# SCH_DengFOC_V3_pro.net
KiCad netlist of a schematic drawn in EasyEDA Pro
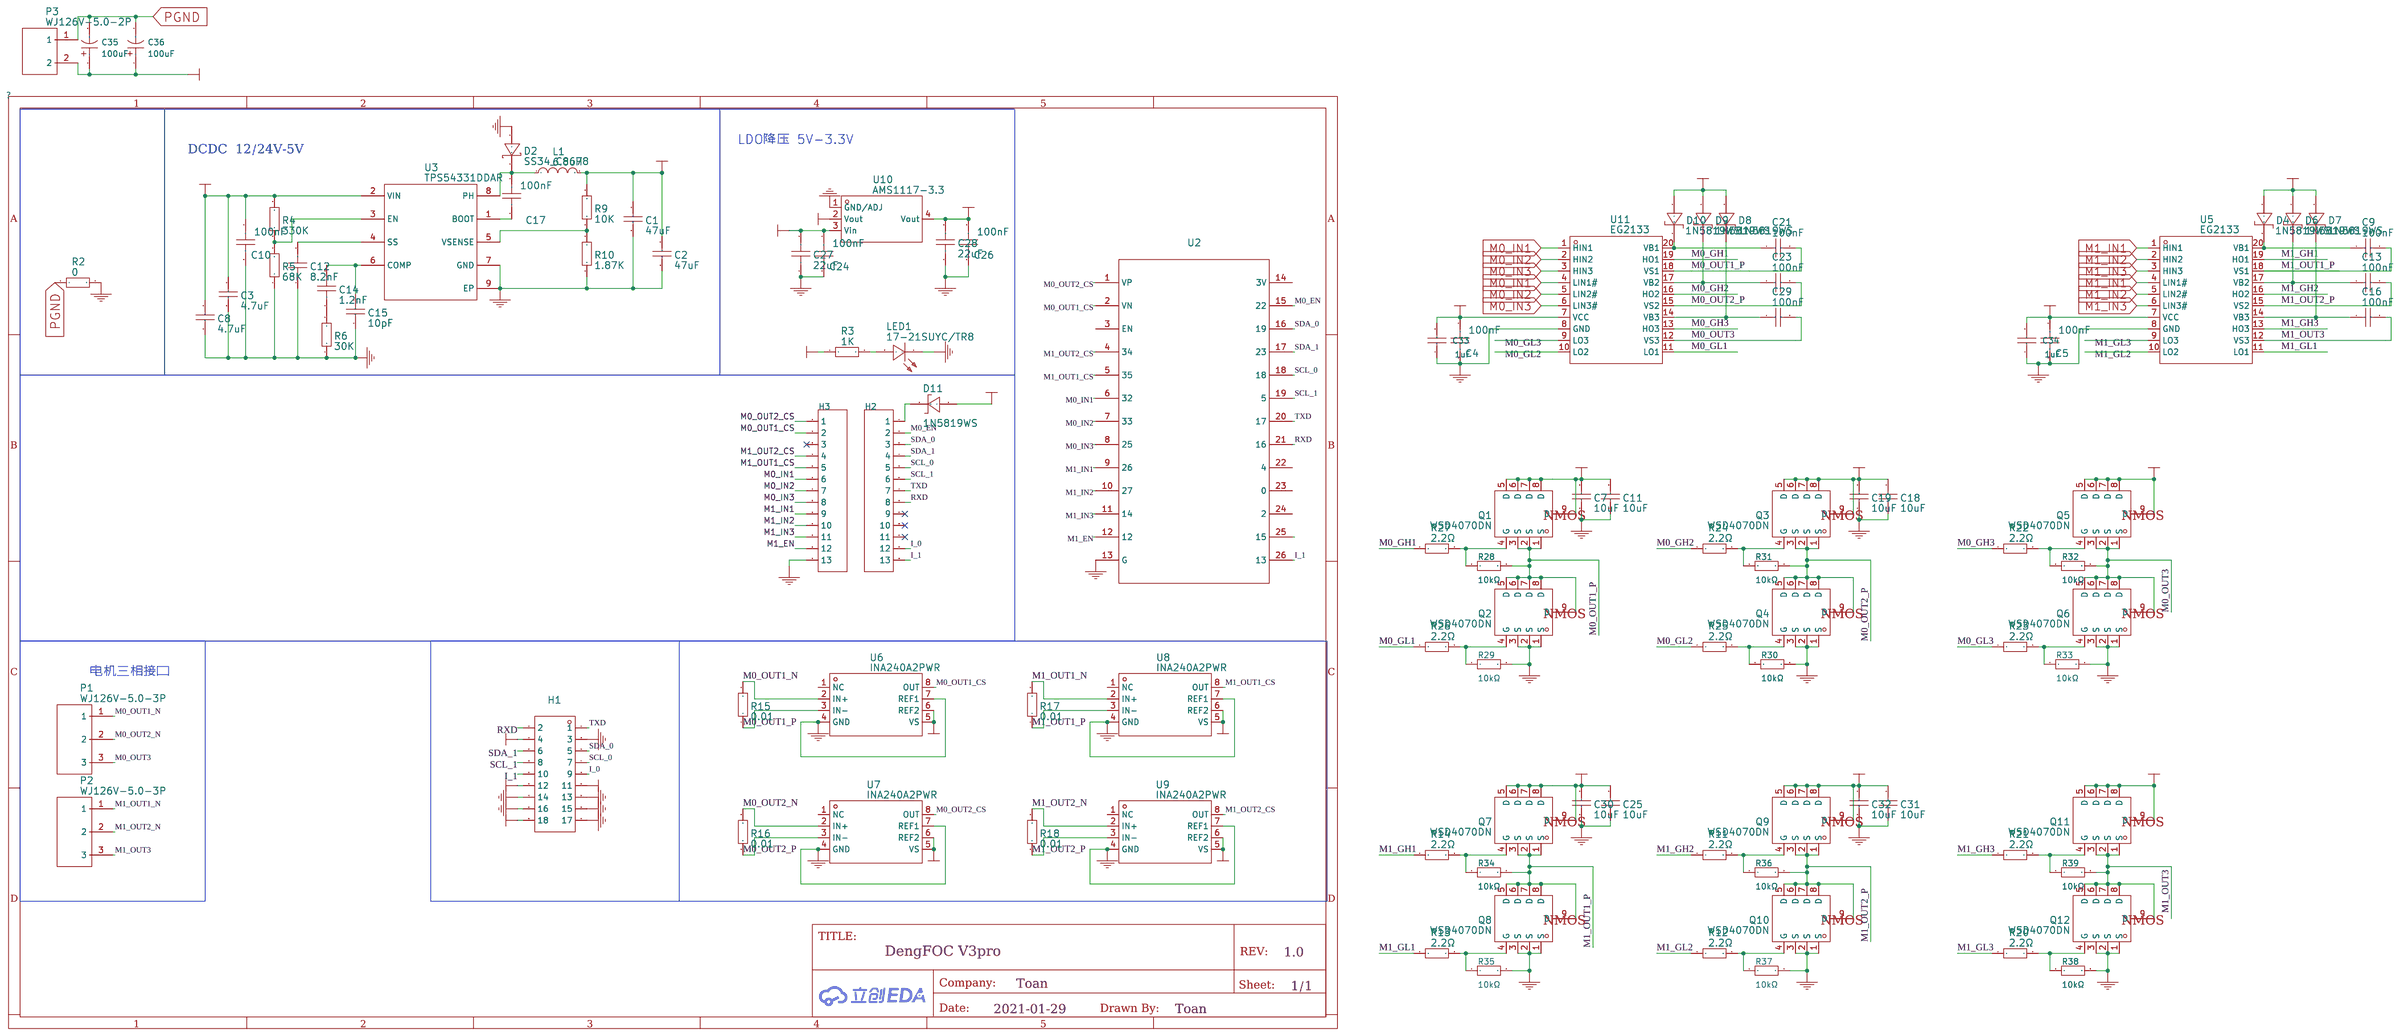
[diagram p0: schematic sheet]

(export (version "E")
  (design (tool "Eeschema 10.0.6"))
  (components
    (comp (ref "C1")
      (value "47uF")
      (footprint "easyedapro:0603")
      (fields (field (name "Manufacturer Part") "GRM188R60J476ME15D") (field (name "Manufacturer") "MuRata"))
      (libsource (lib "easyedapro") (part "47uF"))
    )
    (comp (ref "C2")
      (value "47uF")
      (footprint "easyedapro:0603")
      (fields (field (name "Manufacturer Part") "GRM188R60J476ME15D") (field (name "Manufacturer") "MuRata"))
      (libsource (lib "easyedapro") (part "47uF"))
    )
    (comp (ref "C3")
      (value "4.7uF")
      (footprint "easyedapro:0805")
      (fields (field (name "Manufacturer Part") "CL21A475KBQNNNE") (field (name "Manufacturer") "SAMSUNG"))
      (libsource (lib "easyedapro") (part "4.7uF"))
    )
    (comp (ref "C4")
      (value "100nF")
      (footprint "easyedapro:0603")
      (fields (field (name "Manufacturer Part") "CC0603KRX7R9BB104") (field (name "Manufacturer") "YAGEO"))
      (libsource (lib "") (part "100nF_1"))
    )
    (comp (ref "C5")
      (value "100nF")
      (footprint "easyedapro:0603")
      (fields (field (name "Manufacturer Part") "CC0603KRX7R9BB104") (field (name "Manufacturer") "YAGEO"))
      (libsource (lib "") (part "100nF_1"))
    )
    (comp (ref "C7")
      (value "10uF")
      (footprint "easyedapro:0805")
      (fields (field (name "Manufacturer Part") "CL21A106KAYNNNE") (field (name "Manufacturer") "SAMSUNG"))
      (libsource (lib "easyedapro") (part "10uF"))
    )
    (comp (ref "C8")
      (value "4.7uF")
      (footprint "easyedapro:0805")
      (fields (field (name "Manufacturer Part") "CL21A475KBQNNNE") (field (name "Manufacturer") "SAMSUNG"))
      (libsource (lib "easyedapro") (part "4.7uF"))
    )
    (comp (ref "C9")
      (value "100nF")
      (footprint "easyedapro:0402")
      (fields (field (name "Manufacturer Part") "CL05B104KO5NNNC") (field (name "Manufacturer") "SAMSUNG"))
      (libsource (lib "easyedapro") (part "100nF"))
    )
    (comp (ref "C10")
      (value "100nF")
      (footprint "easyedapro:0603")
      (fields (field (name "Manufacturer Part") "CC0603KRX7R9BB104") (field (name "Manufacturer") "YAGEO"))
      (libsource (lib "") (part "100nF_1"))
    )
    (comp (ref "C11")
      (value "10uF")
      (footprint "easyedapro:0805")
      (fields (field (name "Manufacturer Part") "CL21A106KAYNNNE") (field (name "Manufacturer") "SAMSUNG"))
      (libsource (lib "easyedapro") (part "10uF"))
    )
    (comp (ref "C12")
      (value "8.2nF")
      (footprint "easyedapro:0603")
      (fields (field (name "Manufacturer Part") "CL10B822KB8NNNC") (field (name "Manufacturer") "SAMSUNG"))
      (libsource (lib "easyedapro") (part "8.2nF"))
    )
    (comp (ref "C13")
      (value "100nF")
      (footprint "easyedapro:0402")
      (fields (field (name "Manufacturer Part") "CL05B104KO5NNNC") (field (name "Manufacturer") "SAMSUNG"))
      (libsource (lib "easyedapro") (part "100nF"))
    )
    (comp (ref "C14")
      (value "1.2nF")
      (footprint "easyedapro:0603")
      (fields
        (field (name "Manufacturer Part") "FN18X122K500PSG")
        (field (name "Manufacturer") "PSA(Prosperity Dielectrics)")
      )
      (libsource (lib "easyedapro") (part "1.2nF"))
    )
    (comp (ref "C15")
      (value "10pF")
      (footprint "easyedapro:0603")
      (fields (field (name "Manufacturer Part") "CC0603JRNPO9BN100") (field (name "Manufacturer") "YAGEO"))
      (libsource (lib "easyedapro") (part "10pF"))
    )
    (comp (ref "C16")
      (value "100nF")
      (footprint "easyedapro:0402")
      (fields (field (name "Manufacturer Part") "CL05B104KO5NNNC") (field (name "Manufacturer") "SAMSUNG"))
      (libsource (lib "easyedapro") (part "100nF"))
    )
    (comp (ref "C17")
      (value "100nF")
      (footprint "easyedapro:0603")
      (fields (field (name "Manufacturer Part") "CC0603KRX7R9BB104") (field (name "Manufacturer") "YAGEO"))
      (libsource (lib "") (part "100nF_1"))
    )
    (comp (ref "C18")
      (value "10uF")
      (footprint "easyedapro:0805")
      (fields (field (name "Manufacturer Part") "CL21A106KAYNNNE") (field (name "Manufacturer") "SAMSUNG"))
      (libsource (lib "easyedapro") (part "10uF"))
    )
    (comp (ref "C19")
      (value "10uF")
      (footprint "easyedapro:0805")
      (fields (field (name "Manufacturer Part") "CL21A106KAYNNNE") (field (name "Manufacturer") "SAMSUNG"))
      (libsource (lib "easyedapro") (part "10uF"))
    )
    (comp (ref "C21")
      (value "100nF")
      (footprint "easyedapro:0402")
      (fields (field (name "Manufacturer Part") "CL05B104KO5NNNC") (field (name "Manufacturer") "SAMSUNG"))
      (libsource (lib "easyedapro") (part "100nF"))
    )
    (comp (ref "C23")
      (value "100nF")
      (footprint "easyedapro:0402")
      (fields (field (name "Manufacturer Part") "CL05B104KO5NNNC") (field (name "Manufacturer") "SAMSUNG"))
      (libsource (lib "easyedapro") (part "100nF"))
    )
    (comp (ref "C24")
      (value "100nF")
      (footprint "easyedapro:0603")
      (fields (field (name "Manufacturer Part") "CC0603KRX7R9BB104") (field (name "Manufacturer") "YAGEO"))
      (libsource (lib "") (part "100nF_1"))
    )
    (comp (ref "C25")
      (value "10uF")
      (footprint "easyedapro:0805")
      (fields (field (name "Manufacturer Part") "CL21A106KAYNNNE") (field (name "Manufacturer") "SAMSUNG"))
      (libsource (lib "easyedapro") (part "10uF"))
    )
    (comp (ref "C26")
      (value "100nF")
      (footprint "easyedapro:0603")
      (fields (field (name "Manufacturer Part") "CC0603KRX7R9BB104") (field (name "Manufacturer") "YAGEO"))
      (libsource (lib "") (part "100nF_1"))
    )
    (comp (ref "C27")
      (value "22uF")
      (footprint "easyedapro:0603")
      (fields (field (name "Manufacturer Part") "CL10A226MQ8NRNC") (field (name "Manufacturer") "SAMSUNG"))
      (libsource (lib "easyedapro") (part "22uF"))
    )
    (comp (ref "C28")
      (value "22uF")
      (footprint "easyedapro:0603")
      (fields (field (name "Manufacturer Part") "CL10A226MQ8NRNC") (field (name "Manufacturer") "SAMSUNG"))
      (libsource (lib "easyedapro") (part "22uF"))
    )
    (comp (ref "C29")
      (value "100nF")
      (footprint "easyedapro:0402")
      (fields (field (name "Manufacturer Part") "CL05B104KO5NNNC") (field (name "Manufacturer") "SAMSUNG"))
      (libsource (lib "easyedapro") (part "100nF"))
    )
    (comp (ref "C30")
      (value "10uF")
      (footprint "easyedapro:0805")
      (fields (field (name "Manufacturer Part") "CL21A106KAYNNNE") (field (name "Manufacturer") "SAMSUNG"))
      (libsource (lib "easyedapro") (part "10uF"))
    )
    (comp (ref "C31")
      (value "10uF")
      (footprint "easyedapro:0805")
      (fields (field (name "Manufacturer Part") "CL21A106KAYNNNE") (field (name "Manufacturer") "SAMSUNG"))
      (libsource (lib "easyedapro") (part "10uF"))
    )
    (comp (ref "C32")
      (value "10uF")
      (footprint "easyedapro:0805")
      (fields (field (name "Manufacturer Part") "CL21A106KAYNNNE") (field (name "Manufacturer") "SAMSUNG"))
      (libsource (lib "easyedapro") (part "10uF"))
    )
    (comp (ref "C33")
      (value "1uF")
      (footprint "easyedapro:C0603")
      (description "容值:1uF;精度:±10%;额定电压:50V;材质(温度系数):X5R;")
      (fields
        (field (name "Manufacturer Part") "CL10A105KB8NNNC")
        (field (name "Manufacturer") "SAMSUNG(三星)")
      )
      (libsource (lib "easyedapro") (part "CL10A105KB8NNNC"))
    )
    (comp (ref "C34")
      (value "1uF")
      (footprint "easyedapro:C0603")
      (description "容值:1uF;精度:±10%;额定电压:50V;材质(温度系数):X5R;")
      (fields
        (field (name "Manufacturer Part") "CL10A105KB8NNNC")
        (field (name "Manufacturer") "SAMSUNG(三星)")
      )
      (libsource (lib "easyedapro") (part "CL10A105KB8NNNC"))
    )
    (comp (ref "C35")
      (value "100uF")
      (footprint "easyedapro:CAP-SMD_BD6.3-L6.6-W6.6-LS7.4-FD")
      (description "容值:100uF;精度:±20%;额定电压:35V;纹波电流:87mA@120kHz;等效串联电阻:-;")
      (fields
        (field (name "Manufacturer Part") "RVT100UF35V67RV0034")
        (field (name "Manufacturer") "KNSCHA(科尼盛)")
      )
      (libsource (lib "easyedapro") (part "RVT100UF35V67RV0034"))
    )
    (comp (ref "C36")
      (value "100uF")
      (footprint "easyedapro:CAP-SMD_BD6.3-L6.6-W6.6-LS7.4-FD")
      (description "容值:100uF;精度:±20%;额定电压:35V;纹波电流:87mA@120kHz;等效串联电阻:-;")
      (fields
        (field (name "Manufacturer Part") "RVT100UF35V67RV0034")
        (field (name "Manufacturer") "KNSCHA(科尼盛)")
      )
      (libsource (lib "easyedapro") (part "RVT100UF35V67RV0034"))
    )
    (comp (ref "D2")
      (value "SS34_C8678")
      (footprint "easyedapro:DO-214AC_L4.3-W2.7-LS5.3-RD")
      (fields (field (name "Manufacturer Part") "SS34") (field (name "Manufacturer") "MDD"))
      (libsource (lib "easyedapro") (part "SS34_C8678"))
    )
    (comp (ref "D4")
      (value "1N5819WS")
      (footprint "easyedapro:SOD-323_L1.8-W1.3-LS2.5-RD")
      (fields (field (name "Manufacturer") "Guangdong Hottech"))
      (libsource (lib "easyedapro") (part "1N5819WS"))
    )
    (comp (ref "D6")
      (value "1N5819WS")
      (footprint "easyedapro:SOD-323_L1.8-W1.3-LS2.5-RD")
      (fields (field (name "Manufacturer") "Guangdong Hottech"))
      (libsource (lib "easyedapro") (part "1N5819WS"))
    )
    (comp (ref "D7")
      (value "1N5819WS")
      (footprint "easyedapro:SOD-323_L1.8-W1.3-LS2.5-RD")
      (fields (field (name "Manufacturer") "Guangdong Hottech"))
      (libsource (lib "easyedapro") (part "1N5819WS"))
    )
    (comp (ref "D8")
      (value "1N5819WS")
      (footprint "easyedapro:SOD-323_L1.8-W1.3-LS2.5-RD")
      (fields (field (name "Manufacturer") "Guangdong Hottech"))
      (libsource (lib "easyedapro") (part "1N5819WS"))
    )
    (comp (ref "D9")
      (value "1N5819WS")
      (footprint "easyedapro:SOD-323_L1.8-W1.3-LS2.5-RD")
      (fields (field (name "Manufacturer") "Guangdong Hottech"))
      (libsource (lib "easyedapro") (part "1N5819WS"))
    )
    (comp (ref "D10")
      (value "1N5819WS")
      (footprint "easyedapro:SOD-323_L1.8-W1.3-LS2.5-RD")
      (fields (field (name "Manufacturer") "Guangdong Hottech"))
      (libsource (lib "easyedapro") (part "1N5819WS"))
    )
    (comp (ref "D11")
      (value "1N5819WS")
      (footprint "easyedapro:SOD-323_L1.8-W1.3-LS2.5-RD")
      (fields (field (name "Manufacturer") "Guangdong Hottech"))
      (libsource (lib "easyedapro") (part "1N5819WS"))
    )
    (comp (ref "H1")
      (value "Header-Female-2.54_2x9")
      (footprint "easyedapro:HDR-TH_18P-P2.54-V-R2-C9-S2.54")
      (fields (field (name "Manufacturer") "BOOMELE"))
      (libsource (lib "easyedapro") (part "Header-Female-2.54_2x9"))
    )
    (comp (ref "H2")
      (value "~")
      (footprint "easyedapro:HDR-TH_13P-P2.54-V-F")
      (libsource (lib "easyedapro") (part "HDR-F_2.54_1x13P"))
    )
    (comp (ref "H3")
      (value "~")
      (footprint "easyedapro:HDR-TH_13P-P2.54-V-F")
      (libsource (lib "easyedapro") (part "HDR-F_2.54_1x13P"))
    )
    (comp (ref "L1")
      (value "6.8uH")
      (footprint "easyedapro:IND-SMD_L5.0-W5.0_SWPA5040S")
      (fields (field (name "Manufacturer Part") "SWPA5040S6R8M") (field (name "Manufacturer") "Sunlord"))
      (libsource (lib "easyedapro") (part "6.8uH"))
    )
    (comp (ref "LED1")
      (value "17-21SUYC/TR8")
      (footprint "easyedapro:LED0805-RD")
      (fields (field (name "Manufacturer") "KENTO"))
      (libsource (lib "easyedapro") (part "17-21SUYC/TR8"))
    )
    (comp (ref "P1")
      (value "WJ126V-5.0-3P")
      (footprint "easyedapro:CONN-TH_3P-P5.00_WJ126V-5.0-3P")
      (fields (field (name "Manufacturer") "ReliaPro"))
      (libsource (lib "easyedapro") (part "WJ126V-5.0-3P"))
    )
    (comp (ref "P2")
      (value "WJ126V-5.0-3P")
      (footprint "easyedapro:CONN-TH_3P-P5.00_WJ126V-5.0-3P")
      (fields (field (name "Manufacturer") "ReliaPro"))
      (libsource (lib "easyedapro") (part "WJ126V-5.0-3P"))
    )
    (comp (ref "P3")
      (value "WJ126V-5.0-2P")
      (footprint "easyedapro:CONN-TH_WJ126V-5.0-2P")
      (fields (field (name "Manufacturer") "ReliaPro"))
      (libsource (lib "easyedapro") (part "WJ126V-5.0-2P"))
    )
    (comp (ref "Q1")
      (value "WSD4070DN")
      (footprint "easyedapro:PDFN3333-8_L3.1-W3.2-P0.65-LS3.4-BL")
      (fields (field (name "Manufacturer") "Winsok Semicon"))
      (libsource (lib "easyedapro") (part "WSD4070DN"))
    )
    (comp (ref "Q2")
      (value "WSD4070DN")
      (footprint "easyedapro:PDFN3333-8_L3.1-W3.2-P0.65-LS3.4-BL")
      (fields (field (name "Manufacturer") "Winsok Semicon"))
      (libsource (lib "easyedapro") (part "WSD4070DN"))
    )
    (comp (ref "Q3")
      (value "WSD4070DN")
      (footprint "easyedapro:PDFN3333-8_L3.1-W3.2-P0.65-LS3.4-BL")
      (fields (field (name "Manufacturer") "Winsok Semicon"))
      (libsource (lib "easyedapro") (part "WSD4070DN"))
    )
    (comp (ref "Q4")
      (value "WSD4070DN")
      (footprint "easyedapro:PDFN3333-8_L3.1-W3.2-P0.65-LS3.4-BL")
      (fields (field (name "Manufacturer") "Winsok Semicon"))
      (libsource (lib "easyedapro") (part "WSD4070DN"))
    )
    (comp (ref "Q5")
      (value "WSD4070DN")
      (footprint "easyedapro:PDFN3333-8_L3.1-W3.2-P0.65-LS3.4-BL")
      (fields (field (name "Manufacturer") "Winsok Semicon"))
      (libsource (lib "easyedapro") (part "WSD4070DN"))
    )
    (comp (ref "Q6")
      (value "WSD4070DN")
      (footprint "easyedapro:PDFN3333-8_L3.1-W3.2-P0.65-LS3.4-BL")
      (fields (field (name "Manufacturer") "Winsok Semicon"))
      (libsource (lib "easyedapro") (part "WSD4070DN"))
    )
    (comp (ref "Q7")
      (value "WSD4070DN")
      (footprint "easyedapro:PDFN3333-8_L3.1-W3.2-P0.65-LS3.4-BL")
      (fields (field (name "Manufacturer") "Winsok Semicon"))
      (libsource (lib "easyedapro") (part "WSD4070DN"))
    )
    (comp (ref "Q8")
      (value "WSD4070DN")
      (footprint "easyedapro:PDFN3333-8_L3.1-W3.2-P0.65-LS3.4-BL")
      (fields (field (name "Manufacturer") "Winsok Semicon"))
      (libsource (lib "easyedapro") (part "WSD4070DN"))
    )
    (comp (ref "Q9")
      (value "WSD4070DN")
      (footprint "easyedapro:PDFN3333-8_L3.1-W3.2-P0.65-LS3.4-BL")
      (fields (field (name "Manufacturer") "Winsok Semicon"))
      (libsource (lib "easyedapro") (part "WSD4070DN"))
    )
    (comp (ref "Q10")
      (value "WSD4070DN")
      (footprint "easyedapro:PDFN3333-8_L3.1-W3.2-P0.65-LS3.4-BL")
      (fields (field (name "Manufacturer") "Winsok Semicon"))
      (libsource (lib "easyedapro") (part "WSD4070DN"))
    )
    (comp (ref "Q11")
      (value "WSD4070DN")
      (footprint "easyedapro:PDFN3333-8_L3.1-W3.2-P0.65-LS3.4-BL")
      (fields (field (name "Manufacturer") "Winsok Semicon"))
      (libsource (lib "easyedapro") (part "WSD4070DN"))
    )
    (comp (ref "Q12")
      (value "WSD4070DN")
      (footprint "easyedapro:PDFN3333-8_L3.1-W3.2-P0.65-LS3.4-BL")
      (fields (field (name "Manufacturer") "Winsok Semicon"))
      (libsource (lib "easyedapro") (part "WSD4070DN"))
    )
    (comp (ref "R2")
      (value "0")
      (footprint "easyedapro:0805")
      (fields (field (name "Manufacturer Part") "RM10FTN0") (field (name "Manufacturer") "TA-I Tech"))
      (libsource (lib "easyedapro") (part "0"))
    )
    (comp (ref "R3")
      (value "1K")
      (footprint "easyedapro:0805")
      (fields (field (name "Manufacturer Part") "0805W8F1001T5E") (field (name "Manufacturer") "UniOhm"))
      (libsource (lib "easyedapro") (part "1K"))
    )
    (comp (ref "R4")
      (value "330K")
      (footprint "easyedapro:0603")
      (fields (field (name "Manufacturer Part") "0603WAF3303T5E") (field (name "Manufacturer") "UniOhm"))
      (libsource (lib "easyedapro") (part "330K"))
    )
    (comp (ref "R5")
      (value "68K")
      (footprint "easyedapro:0603")
      (fields (field (name "Manufacturer Part") "0603WAF6802T5E") (field (name "Manufacturer") "UniOhm"))
      (libsource (lib "easyedapro") (part "68K"))
    )
    (comp (ref "R6")
      (value "30K")
      (footprint "easyedapro:0603")
      (fields (field (name "Manufacturer Part") "0603WAF3002T5E") (field (name "Manufacturer") "UniOhm"))
      (libsource (lib "easyedapro") (part "30K"))
    )
    (comp (ref "R9")
      (value "10K")
      (footprint "easyedapro:0603")
      (fields (field (name "Manufacturer Part") "0603WAF1002T5E") (field (name "Manufacturer") "UniOhm"))
      (libsource (lib "easyedapro") (part "10K"))
    )
    (comp (ref "R10")
      (value "1.87K")
      (footprint "easyedapro:0603")
      (fields (field (name "Manufacturer Part") "0603WAF1871T5E") (field (name "Manufacturer") "UniOhm"))
      (libsource (lib "easyedapro") (part "1.87K"))
    )
    (comp (ref "R11")
      (value "2.2Ω")
      (footprint "easyedapro:0402")
      (fields (field (name "Manufacturer Part") "0603WAF100JT5E") (field (name "Manufacturer") "UniOhm"))
      (libsource (lib "easyedapro") (part "10Ω"))
    )
    (comp (ref "R12")
      (value "2.2Ω")
      (footprint "easyedapro:0402")
      (fields (field (name "Manufacturer Part") "0603WAF100JT5E") (field (name "Manufacturer") "UniOhm"))
      (libsource (lib "easyedapro") (part "10Ω"))
    )
    (comp (ref "R13")
      (value "2.2Ω")
      (footprint "easyedapro:0402")
      (fields (field (name "Manufacturer Part") "0603WAF100JT5E") (field (name "Manufacturer") "UniOhm"))
      (libsource (lib "easyedapro") (part "10Ω"))
    )
    (comp (ref "R14")
      (value "2.2Ω")
      (footprint "easyedapro:0402")
      (fields (field (name "Manufacturer Part") "0603WAF100JT5E") (field (name "Manufacturer") "UniOhm"))
      (libsource (lib "easyedapro") (part "10Ω"))
    )
    (comp (ref "R15")
      (value "0.01")
      (footprint "easyedapro:R1206")
      (fields (field (name "Manufacturer Part") "RTT06R010FTP") (field (name "Manufacturer") "RALEC"))
      (libsource (lib "easyedapro") (part "0.01"))
    )
    (comp (ref "R16")
      (value "0.01")
      (footprint "easyedapro:R1206")
      (fields (field (name "Manufacturer Part") "RTT06R010FTP") (field (name "Manufacturer") "RALEC"))
      (libsource (lib "easyedapro") (part "0.01"))
    )
    (comp (ref "R17")
      (value "0.01")
      (footprint "easyedapro:R1206")
      (fields (field (name "Manufacturer Part") "RTT06R010FTP") (field (name "Manufacturer") "RALEC"))
      (libsource (lib "easyedapro") (part "0.01"))
    )
    (comp (ref "R18")
      (value "0.01")
      (footprint "easyedapro:R1206")
      (fields (field (name "Manufacturer Part") "RTT06R010FTP") (field (name "Manufacturer") "RALEC"))
      (libsource (lib "easyedapro") (part "0.01"))
    )
    (comp (ref "R20")
      (value "2.2Ω")
      (footprint "easyedapro:0402")
      (fields (field (name "Manufacturer Part") "0603WAF100JT5E") (field (name "Manufacturer") "UniOhm"))
      (libsource (lib "easyedapro") (part "10Ω"))
    )
    (comp (ref "R21")
      (value "2.2Ω")
      (footprint "easyedapro:0402")
      (fields (field (name "Manufacturer Part") "0603WAF100JT5E") (field (name "Manufacturer") "UniOhm"))
      (libsource (lib "easyedapro") (part "10Ω"))
    )
    (comp (ref "R22")
      (value "2.2Ω")
      (footprint "easyedapro:0402")
      (fields (field (name "Manufacturer Part") "0603WAF100JT5E") (field (name "Manufacturer") "UniOhm"))
      (libsource (lib "easyedapro") (part "10Ω"))
    )
    (comp (ref "R23")
      (value "2.2Ω")
      (footprint "easyedapro:0402")
      (fields (field (name "Manufacturer Part") "0603WAF100JT5E") (field (name "Manufacturer") "UniOhm"))
      (libsource (lib "easyedapro") (part "10Ω"))
    )
    (comp (ref "R24")
      (value "2.2Ω")
      (footprint "easyedapro:0402")
      (fields (field (name "Manufacturer Part") "0603WAF100JT5E") (field (name "Manufacturer") "UniOhm"))
      (libsource (lib "easyedapro") (part "10Ω"))
    )
    (comp (ref "R25")
      (value "2.2Ω")
      (footprint "easyedapro:0402")
      (fields (field (name "Manufacturer Part") "0603WAF100JT5E") (field (name "Manufacturer") "UniOhm"))
      (libsource (lib "easyedapro") (part "10Ω"))
    )
    (comp (ref "R26")
      (value "2.2Ω")
      (footprint "easyedapro:0402")
      (fields (field (name "Manufacturer Part") "0603WAF100JT5E") (field (name "Manufacturer") "UniOhm"))
      (libsource (lib "easyedapro") (part "10Ω"))
    )
    (comp (ref "R27")
      (value "2.2Ω")
      (footprint "easyedapro:0402")
      (fields (field (name "Manufacturer Part") "0603WAF100JT5E") (field (name "Manufacturer") "UniOhm"))
      (libsource (lib "easyedapro") (part "10Ω"))
    )
    (comp (ref "R28")
      (value "10kΩ")
      (footprint "easyedapro:R0402")
      (description "电阻类型:厚膜电阻;阻值:10kΩ;精度:±1%;功率:62.5mW;")
      (fields
        (field (name "Manufacturer Part") "0402WGF1002TCE")
        (field (name "Manufacturer") "UNI-ROYAL(厚声)")
      )
      (libsource (lib "easyedapro") (part "0402WGF1002TCE"))
    )
    (comp (ref "R29")
      (value "10kΩ")
      (footprint "easyedapro:R0402")
      (description "电阻类型:厚膜电阻;阻值:10kΩ;精度:±1%;功率:62.5mW;")
      (fields
        (field (name "Manufacturer Part") "0402WGF1002TCE")
        (field (name "Manufacturer") "UNI-ROYAL(厚声)")
      )
      (libsource (lib "easyedapro") (part "0402WGF1002TCE"))
    )
    (comp (ref "R30")
      (value "10kΩ")
      (footprint "easyedapro:R0402")
      (description "电阻类型:厚膜电阻;阻值:10kΩ;精度:±1%;功率:62.5mW;")
      (fields
        (field (name "Manufacturer Part") "0402WGF1002TCE")
        (field (name "Manufacturer") "UNI-ROYAL(厚声)")
      )
      (libsource (lib "easyedapro") (part "0402WGF1002TCE"))
    )
    (comp (ref "R31")
      (value "10kΩ")
      (footprint "easyedapro:R0402")
      (description "电阻类型:厚膜电阻;阻值:10kΩ;精度:±1%;功率:62.5mW;")
      (fields
        (field (name "Manufacturer Part") "0402WGF1002TCE")
        (field (name "Manufacturer") "UNI-ROYAL(厚声)")
      )
      (libsource (lib "easyedapro") (part "0402WGF1002TCE"))
    )
    (comp (ref "R32")
      (value "10kΩ")
      (footprint "easyedapro:R0402")
      (description "电阻类型:厚膜电阻;阻值:10kΩ;精度:±1%;功率:62.5mW;")
      (fields
        (field (name "Manufacturer Part") "0402WGF1002TCE")
        (field (name "Manufacturer") "UNI-ROYAL(厚声)")
      )
      (libsource (lib "easyedapro") (part "0402WGF1002TCE"))
    )
    (comp (ref "R33")
      (value "10kΩ")
      (footprint "easyedapro:R0402")
      (description "电阻类型:厚膜电阻;阻值:10kΩ;精度:±1%;功率:62.5mW;")
      (fields
        (field (name "Manufacturer Part") "0402WGF1002TCE")
        (field (name "Manufacturer") "UNI-ROYAL(厚声)")
      )
      (libsource (lib "easyedapro") (part "0402WGF1002TCE"))
    )
    (comp (ref "R34")
      (value "10kΩ")
      (footprint "easyedapro:R0402")
      (description "电阻类型:厚膜电阻;阻值:10kΩ;精度:±1%;功率:62.5mW;")
      (fields
        (field (name "Manufacturer Part") "0402WGF1002TCE")
        (field (name "Manufacturer") "UNI-ROYAL(厚声)")
      )
      (libsource (lib "easyedapro") (part "0402WGF1002TCE"))
    )
    (comp (ref "R35")
      (value "10kΩ")
      (footprint "easyedapro:R0402")
      (description "电阻类型:厚膜电阻;阻值:10kΩ;精度:±1%;功率:62.5mW;")
      (fields
        (field (name "Manufacturer Part") "0402WGF1002TCE")
        (field (name "Manufacturer") "UNI-ROYAL(厚声)")
      )
      (libsource (lib "easyedapro") (part "0402WGF1002TCE"))
    )
    (comp (ref "R36")
      (value "10kΩ")
      (footprint "easyedapro:R0402")
      (description "电阻类型:厚膜电阻;阻值:10kΩ;精度:±1%;功率:62.5mW;")
      (fields
        (field (name "Manufacturer Part") "0402WGF1002TCE")
        (field (name "Manufacturer") "UNI-ROYAL(厚声)")
      )
      (libsource (lib "easyedapro") (part "0402WGF1002TCE"))
    )
    (comp (ref "R37")
      (value "10kΩ")
      (footprint "easyedapro:R0402")
      (description "电阻类型:厚膜电阻;阻值:10kΩ;精度:±1%;功率:62.5mW;")
      (fields
        (field (name "Manufacturer Part") "0402WGF1002TCE")
        (field (name "Manufacturer") "UNI-ROYAL(厚声)")
      )
      (libsource (lib "easyedapro") (part "0402WGF1002TCE"))
    )
    (comp (ref "R38")
      (value "10kΩ")
      (footprint "easyedapro:R0402")
      (description "电阻类型:厚膜电阻;阻值:10kΩ;精度:±1%;功率:62.5mW;")
      (fields
        (field (name "Manufacturer Part") "0402WGF1002TCE")
        (field (name "Manufacturer") "UNI-ROYAL(厚声)")
      )
      (libsource (lib "easyedapro") (part "0402WGF1002TCE"))
    )
    (comp (ref "R39")
      (value "10kΩ")
      (footprint "easyedapro:R0402")
      (description "电阻类型:厚膜电阻;阻值:10kΩ;精度:±1%;功率:62.5mW;")
      (fields
        (field (name "Manufacturer Part") "0402WGF1002TCE")
        (field (name "Manufacturer") "UNI-ROYAL(厚声)")
      )
      (libsource (lib "easyedapro") (part "0402WGF1002TCE"))
    )
    (comp (ref "U2")
      (value "micropython esp32")
      (footprint "easyedapro:MICROPYTHON ESP32")
      (libsource (lib "easyedapro") (part "micropython esp32"))
    )
    (comp (ref "U3")
      (value "TPS54331DDAR")
      (footprint "easyedapro:SOIC-8_L5.0-W4.0-P1.27-LS6.0-BL-EP")
      (fields (field (name "Manufacturer") "TI"))
      (libsource (lib "easyedapro") (part "TPS54331DDAR"))
    )
    (comp (ref "U5")
      (value "EG2133")
      (footprint "easyedapro:TSSOP-20_L6.5-W4.4-P0.65-LS6.4-BL")
      (fields (field (name "Manufacturer") "EG Micro"))
      (libsource (lib "easyedapro") (part "EG2133"))
    )
    (comp (ref "U6")
      (value "INA240A2PWR")
      (footprint "easyedapro:TSSOP-8_L4.4-W3.0-P0.65-LS6.4-BL")
      (fields (field (name "Manufacturer") "TI"))
      (libsource (lib "easyedapro") (part "INA240A2PWR"))
    )
    (comp (ref "U7")
      (value "INA240A2PWR")
      (footprint "easyedapro:TSSOP-8_L4.4-W3.0-P0.65-LS6.4-BL")
      (fields (field (name "Manufacturer") "TI"))
      (libsource (lib "easyedapro") (part "INA240A2PWR"))
    )
    (comp (ref "U8")
      (value "INA240A2PWR")
      (footprint "easyedapro:TSSOP-8_L4.4-W3.0-P0.65-LS6.4-BL")
      (fields (field (name "Manufacturer") "TI"))
      (libsource (lib "easyedapro") (part "INA240A2PWR"))
    )
    (comp (ref "U9")
      (value "INA240A2PWR")
      (footprint "easyedapro:TSSOP-8_L4.4-W3.0-P0.65-LS6.4-BL")
      (fields (field (name "Manufacturer") "TI"))
      (libsource (lib "easyedapro") (part "INA240A2PWR"))
    )
    (comp (ref "U10")
      (value "AMS1117-3.3")
      (footprint "easyedapro:SOT-223-4_L6.5-W3.5-P2.30-LS7.0-BR")
      (fields (field (name "Manufacturer") "AMS"))
      (libsource (lib "easyedapro") (part "AMS1117-3.3"))
    )
    (comp (ref "U11")
      (value "EG2133")
      (footprint "easyedapro:TSSOP-20_L6.5-W4.4-P0.65-LS6.4-BL")
      (fields (field (name "Manufacturer") "EG Micro"))
      (libsource (lib "easyedapro") (part "EG2133"))
    )
  )
  (nets
    (net (code "1") (name "/I_0") (class "Default")
      (node (ref "H1") (pin "9") (pinfunction "9_9") (pintype "input"))
      (node (ref "H2") (pin "12") (pinfunction "12_12") (pintype "input"))
    )
    (net (code "2") (name "/I_1") (class "Default")
      (node (ref "H1") (pin "10") (pinfunction "10_10") (pintype "input"))
      (node (ref "H2") (pin "13") (pinfunction "13_13") (pintype "input"))
      (node (ref "U2") (pin "26") (pinfunction "13_26") (pintype "input"))
    )
    (net (code "3") (name "/M0_EN") (class "Default")
      (node (ref "H2") (pin "2") (pinfunction "2_2") (pintype "input"))
      (node (ref "U2") (pin "15") (pinfunction "22_15") (pintype "input"))
    )
    (net (code "4") (name "/M0_GH1") (class "Default")
      (node (ref "R27") (pin "1") (pinfunction "1_1") (pintype "input"))
      (node (ref "U11") (pin "19") (pinfunction "HO1_19") (pintype "input"))
    )
    (net (code "5") (name "/M0_GH2") (class "Default")
      (node (ref "R24") (pin "1") (pinfunction "1_1") (pintype "input"))
      (node (ref "U11") (pin "16") (pinfunction "HO2_16") (pintype "input"))
    )
    (net (code "6") (name "/M0_GH3") (class "Default")
      (node (ref "R22") (pin "1") (pinfunction "1_1") (pintype "input"))
      (node (ref "U11") (pin "13") (pinfunction "HO3_13") (pintype "input"))
    )
    (net (code "7") (name "/M0_GL1") (class "Default")
      (node (ref "R26") (pin "1") (pinfunction "1_1") (pintype "input"))
      (node (ref "U11") (pin "11") (pinfunction "LO1_11") (pintype "input"))
    )
    (net (code "8") (name "/M0_GL2") (class "Default")
      (node (ref "R25") (pin "1") (pinfunction "1_1") (pintype "input"))
      (node (ref "U11") (pin "10") (pinfunction "LO2_10") (pintype "input"))
    )
    (net (code "9") (name "/M0_GL3") (class "Default")
      (node (ref "R23") (pin "1") (pinfunction "1_1") (pintype "input"))
      (node (ref "U11") (pin "9") (pinfunction "LO3_9") (pintype "input"))
    )
    (net (code "10") (name "/M0_OUT1_CS") (class "Default")
      (node (ref "H3") (pin "2") (pinfunction "2_2") (pintype "input"))
      (node (ref "U2") (pin "2") (pinfunction "VN_2") (pintype "input"))
      (node (ref "U6") (pin "8") (pinfunction "OUT_8") (pintype "input"))
    )
    (net (code "11") (name "/M0_OUT1_N") (class "Default")
      (node (ref "P1") (pin "1") (pinfunction "1_1") (pintype "input"))
      (node (ref "R15") (pin "2") (pinfunction "2_2") (pintype "input"))
      (node (ref "U6") (pin "2") (pinfunction "IN+_2") (pintype "input"))
    )
    (net (code "12") (name "/M0_OUT1_P") (class "Default")
      (node (ref "C21") (pin "2") (pinfunction "2_2") (pintype "input"))
      (node (ref "Q1") (pin "1") (pinfunction "S_1") (pintype "input"))
      (node (ref "Q1") (pin "2") (pinfunction "S_2") (pintype "input"))
      (node (ref "Q1") (pin "3") (pinfunction "S_3") (pintype "input"))
      (node (ref "Q2") (pin "5") (pinfunction "D_5") (pintype "input"))
      (node (ref "Q2") (pin "6") (pinfunction "D_6") (pintype "input"))
      (node (ref "Q2") (pin "7") (pinfunction "D_7") (pintype "input"))
      (node (ref "Q2") (pin "8") (pinfunction "D_8") (pintype "input"))
      (node (ref "Q2") (pin "9") (pinfunction "D_9") (pintype "input"))
      (node (ref "R15") (pin "1") (pinfunction "1_1") (pintype "input"))
      (node (ref "R28") (pin "2") (pinfunction "2_2") (pintype "input"))
      (node (ref "U11") (pin "18") (pinfunction "VS1_18") (pintype "input"))
      (node (ref "U6") (pin "3") (pinfunction "IN-_3") (pintype "input"))
    )
    (net (code "13") (name "/M0_OUT2_CS") (class "Default")
      (node (ref "H3") (pin "1") (pinfunction "1_1") (pintype "input"))
      (node (ref "U2") (pin "1") (pinfunction "VP_1") (pintype "input"))
      (node (ref "U7") (pin "8") (pinfunction "OUT_8") (pintype "input"))
    )
    (net (code "14") (name "/M0_OUT2_N") (class "Default")
      (node (ref "P1") (pin "2") (pinfunction "2_2") (pintype "input"))
      (node (ref "R16") (pin "2") (pinfunction "2_2") (pintype "input"))
      (node (ref "U7") (pin "2") (pinfunction "IN+_2") (pintype "input"))
    )
    (net (code "15") (name "/M0_OUT2_P") (class "Default")
      (node (ref "C23") (pin "2") (pinfunction "2_2") (pintype "input"))
      (node (ref "Q3") (pin "1") (pinfunction "S_1") (pintype "input"))
      (node (ref "Q3") (pin "2") (pinfunction "S_2") (pintype "input"))
      (node (ref "Q3") (pin "3") (pinfunction "S_3") (pintype "input"))
      (node (ref "Q4") (pin "5") (pinfunction "D_5") (pintype "input"))
      (node (ref "Q4") (pin "6") (pinfunction "D_6") (pintype "input"))
      (node (ref "Q4") (pin "7") (pinfunction "D_7") (pintype "input"))
      (node (ref "Q4") (pin "8") (pinfunction "D_8") (pintype "input"))
      (node (ref "Q4") (pin "9") (pinfunction "D_9") (pintype "input"))
      (node (ref "R16") (pin "1") (pinfunction "1_1") (pintype "input"))
      (node (ref "R31") (pin "2") (pinfunction "2_2") (pintype "input"))
      (node (ref "U11") (pin "15") (pinfunction "VS2_15") (pintype "input"))
      (node (ref "U7") (pin "3") (pinfunction "IN-_3") (pintype "input"))
    )
    (net (code "16") (name "/M0_OUT3") (class "Default")
      (node (ref "C29") (pin "2") (pinfunction "2_2") (pintype "input"))
      (node (ref "P1") (pin "3") (pinfunction "3_3") (pintype "input"))
      (node (ref "Q5") (pin "1") (pinfunction "S_1") (pintype "input"))
      (node (ref "Q5") (pin "2") (pinfunction "S_2") (pintype "input"))
      (node (ref "Q5") (pin "3") (pinfunction "S_3") (pintype "input"))
      (node (ref "Q6") (pin "5") (pinfunction "D_5") (pintype "input"))
      (node (ref "Q6") (pin "6") (pinfunction "D_6") (pintype "input"))
      (node (ref "Q6") (pin "7") (pinfunction "D_7") (pintype "input"))
      (node (ref "Q6") (pin "8") (pinfunction "D_8") (pintype "input"))
      (node (ref "Q6") (pin "9") (pinfunction "D_9") (pintype "input"))
      (node (ref "R32") (pin "2") (pinfunction "2_2") (pintype "input"))
      (node (ref "U11") (pin "12") (pinfunction "VS3_12") (pintype "input"))
    )
    (net (code "17") (name "/M1_EN") (class "Default")
      (node (ref "H3") (pin "12") (pinfunction "12_12") (pintype "input"))
      (node (ref "U2") (pin "12") (pinfunction "12_12") (pintype "input"))
    )
    (net (code "18") (name "/M1_GH1") (class "Default")
      (node (ref "R14") (pin "1") (pinfunction "1_1") (pintype "input"))
      (node (ref "U5") (pin "19") (pinfunction "HO1_19") (pintype "input"))
    )
    (net (code "19") (name "/M1_GH2") (class "Default")
      (node (ref "R11") (pin "1") (pinfunction "1_1") (pintype "input"))
      (node (ref "U5") (pin "16") (pinfunction "HO2_16") (pintype "input"))
    )
    (net (code "20") (name "/M1_GH3") (class "Default")
      (node (ref "R21") (pin "1") (pinfunction "1_1") (pintype "input"))
      (node (ref "U5") (pin "13") (pinfunction "HO3_13") (pintype "input"))
    )
    (net (code "21") (name "/M1_GL1") (class "Default")
      (node (ref "R13") (pin "1") (pinfunction "1_1") (pintype "input"))
      (node (ref "U5") (pin "11") (pinfunction "LO1_11") (pintype "input"))
    )
    (net (code "22") (name "/M1_GL2") (class "Default")
      (node (ref "R12") (pin "1") (pinfunction "1_1") (pintype "input"))
      (node (ref "U5") (pin "10") (pinfunction "LO2_10") (pintype "input"))
    )
    (net (code "23") (name "/M1_GL3") (class "Default")
      (node (ref "R20") (pin "1") (pinfunction "1_1") (pintype "input"))
      (node (ref "U5") (pin "9") (pinfunction "LO3_9") (pintype "input"))
    )
    (net (code "24") (name "/M1_OUT1_CS") (class "Default")
      (node (ref "H3") (pin "5") (pinfunction "5_5") (pintype "input"))
      (node (ref "U2") (pin "5") (pinfunction "35_5") (pintype "input"))
      (node (ref "U8") (pin "8") (pinfunction "OUT_8") (pintype "input"))
    )
    (net (code "25") (name "/M1_OUT1_N") (class "Default")
      (node (ref "P2") (pin "1") (pinfunction "1_1") (pintype "input"))
      (node (ref "R17") (pin "2") (pinfunction "2_2") (pintype "input"))
      (node (ref "U8") (pin "2") (pinfunction "IN+_2") (pintype "input"))
    )
    (net (code "26") (name "/M1_OUT1_P") (class "Default")
      (node (ref "C9") (pin "2") (pinfunction "2_2") (pintype "input"))
      (node (ref "Q7") (pin "1") (pinfunction "S_1") (pintype "input"))
      (node (ref "Q7") (pin "2") (pinfunction "S_2") (pintype "input"))
      (node (ref "Q7") (pin "3") (pinfunction "S_3") (pintype "input"))
      (node (ref "Q8") (pin "5") (pinfunction "D_5") (pintype "input"))
      (node (ref "Q8") (pin "6") (pinfunction "D_6") (pintype "input"))
      (node (ref "Q8") (pin "7") (pinfunction "D_7") (pintype "input"))
      (node (ref "Q8") (pin "8") (pinfunction "D_8") (pintype "input"))
      (node (ref "Q8") (pin "9") (pinfunction "D_9") (pintype "input"))
      (node (ref "R17") (pin "1") (pinfunction "1_1") (pintype "input"))
      (node (ref "R34") (pin "2") (pinfunction "2_2") (pintype "input"))
      (node (ref "U5") (pin "18") (pinfunction "VS1_18") (pintype "input"))
      (node (ref "U8") (pin "3") (pinfunction "IN-_3") (pintype "input"))
    )
    (net (code "27") (name "/M1_OUT2_CS") (class "Default")
      (node (ref "H3") (pin "4") (pinfunction "4_4") (pintype "input"))
      (node (ref "U2") (pin "4") (pinfunction "34_4") (pintype "input"))
      (node (ref "U9") (pin "8") (pinfunction "OUT_8") (pintype "input"))
    )
    (net (code "28") (name "/M1_OUT2_N") (class "Default")
      (node (ref "P2") (pin "2") (pinfunction "2_2") (pintype "input"))
      (node (ref "R18") (pin "2") (pinfunction "2_2") (pintype "input"))
      (node (ref "U9") (pin "2") (pinfunction "IN+_2") (pintype "input"))
    )
    (net (code "29") (name "/M1_OUT2_P") (class "Default")
      (node (ref "C13") (pin "2") (pinfunction "2_2") (pintype "input"))
      (node (ref "Q10") (pin "5") (pinfunction "D_5") (pintype "input"))
      (node (ref "Q10") (pin "6") (pinfunction "D_6") (pintype "input"))
      (node (ref "Q10") (pin "7") (pinfunction "D_7") (pintype "input"))
      (node (ref "Q10") (pin "8") (pinfunction "D_8") (pintype "input"))
      (node (ref "Q10") (pin "9") (pinfunction "D_9") (pintype "input"))
      (node (ref "Q9") (pin "1") (pinfunction "S_1") (pintype "input"))
      (node (ref "Q9") (pin "2") (pinfunction "S_2") (pintype "input"))
      (node (ref "Q9") (pin "3") (pinfunction "S_3") (pintype "input"))
      (node (ref "R18") (pin "1") (pinfunction "1_1") (pintype "input"))
      (node (ref "R36") (pin "2") (pinfunction "2_2") (pintype "input"))
      (node (ref "U5") (pin "15") (pinfunction "VS2_15") (pintype "input"))
      (node (ref "U9") (pin "3") (pinfunction "IN-_3") (pintype "input"))
    )
    (net (code "30") (name "/M1_OUT3") (class "Default")
      (node (ref "C16") (pin "2") (pinfunction "2_2") (pintype "input"))
      (node (ref "P2") (pin "3") (pinfunction "3_3") (pintype "input"))
      (node (ref "Q11") (pin "1") (pinfunction "S_1") (pintype "input"))
      (node (ref "Q11") (pin "2") (pinfunction "S_2") (pintype "input"))
      (node (ref "Q11") (pin "3") (pinfunction "S_3") (pintype "input"))
      (node (ref "Q12") (pin "5") (pinfunction "D_5") (pintype "input"))
      (node (ref "Q12") (pin "6") (pinfunction "D_6") (pintype "input"))
      (node (ref "Q12") (pin "7") (pinfunction "D_7") (pintype "input"))
      (node (ref "Q12") (pin "8") (pinfunction "D_8") (pintype "input"))
      (node (ref "Q12") (pin "9") (pinfunction "D_9") (pintype "input"))
      (node (ref "R39") (pin "2") (pinfunction "2_2") (pintype "input"))
      (node (ref "U5") (pin "12") (pinfunction "VS3_12") (pintype "input"))
    )
    (net (code "31") (name "/RXD") (class "Default")
      (node (ref "H1") (pin "2") (pinfunction "2_2") (pintype "input"))
      (node (ref "H2") (pin "8") (pinfunction "8_8") (pintype "input"))
      (node (ref "U2") (pin "21") (pinfunction "16_21") (pintype "input"))
    )
    (net (code "32") (name "/SCL_0") (class "Default")
      (node (ref "H1") (pin "7") (pinfunction "7_7") (pintype "input"))
      (node (ref "H2") (pin "5") (pinfunction "5_5") (pintype "input"))
      (node (ref "U2") (pin "18") (pinfunction "18_18") (pintype "input"))
    )
    (net (code "33") (name "/SCL_1") (class "Default")
      (node (ref "H1") (pin "8") (pinfunction "8_8") (pintype "input"))
      (node (ref "H2") (pin "6") (pinfunction "6_6") (pintype "input"))
      (node (ref "U2") (pin "19") (pinfunction "5_19") (pintype "input"))
    )
    (net (code "34") (name "/SDA_0") (class "Default")
      (node (ref "H1") (pin "5") (pinfunction "5_5") (pintype "input"))
      (node (ref "H2") (pin "3") (pinfunction "3_3") (pintype "input"))
      (node (ref "U2") (pin "16") (pinfunction "19_16") (pintype "input"))
    )
    (net (code "35") (name "/SDA_1") (class "Default")
      (node (ref "H1") (pin "6") (pinfunction "6_6") (pintype "input"))
      (node (ref "H2") (pin "4") (pinfunction "4_4") (pintype "input"))
      (node (ref "U2") (pin "17") (pinfunction "23_17") (pintype "input"))
    )
    (net (code "36") (name "/TXD") (class "Default")
      (node (ref "H1") (pin "1") (pinfunction "1_1") (pintype "input"))
      (node (ref "H2") (pin "7") (pinfunction "7_7") (pintype "input"))
      (node (ref "U2") (pin "20") (pinfunction "17_20") (pintype "input"))
    )
    (net (code "37") (name "3V3") (class "Default")
      (node (ref "C26") (pin "1") (pinfunction "1_1") (pintype "input"))
      (node (ref "C28") (pin "2") (pinfunction "2_2") (pintype "input"))
      (node (ref "D11") (pin "2") (pinfunction "A_2") (pintype "input"))
      (node (ref "H1") (pin "11") (pinfunction "11_11") (pintype "input"))
      (node (ref "H1") (pin "12") (pinfunction "12_12") (pintype "input"))
      (node (ref "H1") (pin "4") (pinfunction "4_4") (pintype "input"))
      (node (ref "R3") (pin "1") (pinfunction "1_1") (pintype "input"))
      (node (ref "U10") (pin "2") (pinfunction "Vout_2") (pintype "input"))
      (node (ref "U10") (pin "4") (pinfunction "Vout_4") (pintype "input"))
      (node (ref "U6") (pin "5") (pinfunction "VS_5") (pintype "input"))
      (node (ref "U6") (pin "6") (pinfunction "REF2_6") (pintype "input"))
      (node (ref "U7") (pin "5") (pinfunction "VS_5") (pintype "input"))
      (node (ref "U7") (pin "6") (pinfunction "REF2_6") (pintype "input"))
      (node (ref "U8") (pin "5") (pinfunction "VS_5") (pintype "input"))
      (node (ref "U8") (pin "6") (pinfunction "REF2_6") (pintype "input"))
      (node (ref "U9") (pin "5") (pinfunction "VS_5") (pintype "input"))
      (node (ref "U9") (pin "6") (pinfunction "REF2_6") (pintype "input"))
    )
    (net (code "38") (name "5V") (class "Default")
      (node (ref "C1") (pin "2") (pinfunction "2_2") (pintype "input"))
      (node (ref "C2") (pin "2") (pinfunction "2_2") (pintype "input"))
      (node (ref "C24") (pin "1") (pinfunction "1_1") (pintype "input"))
      (node (ref "C27") (pin "2") (pinfunction "2_2") (pintype "input"))
      (node (ref "C33") (pin "2") (pinfunction "2_2") (pintype "input"))
      (node (ref "C34") (pin "2") (pinfunction "2_2") (pintype "input"))
      (node (ref "C4") (pin "1") (pinfunction "1_1") (pintype "input"))
      (node (ref "C5") (pin "1") (pinfunction "1_1") (pintype "input"))
      (node (ref "D10") (pin "2") (pinfunction "A_2") (pintype "input"))
      (node (ref "D4") (pin "2") (pinfunction "A_2") (pintype "input"))
      (node (ref "D6") (pin "2") (pinfunction "A_2") (pintype "input"))
      (node (ref "D7") (pin "2") (pinfunction "A_2") (pintype "input"))
      (node (ref "D8") (pin "2") (pinfunction "A_2") (pintype "input"))
      (node (ref "D9") (pin "2") (pinfunction "A_2") (pintype "input"))
      (node (ref "H1") (pin "18") (pinfunction "18_18") (pintype "input"))
      (node (ref "L1") (pin "2") (pinfunction "2_2") (pintype "input"))
      (node (ref "R9") (pin "2") (pinfunction "2_2") (pintype "input"))
      (node (ref "U10") (pin "3") (pinfunction "Vin_3") (pintype "input"))
      (node (ref "U11") (pin "7") (pinfunction "VCC_7") (pintype "input"))
      (node (ref "U5") (pin "7") (pinfunction "VCC_7") (pintype "input"))
    )
    (net (code "39") (name "GND") (class "Default")
      (node (ref "C1") (pin "1") (pinfunction "1_1") (pintype "input"))
      (node (ref "C10") (pin "2") (pinfunction "2_2") (pintype "input"))
      (node (ref "C12") (pin "1") (pinfunction "1_1") (pintype "input"))
      (node (ref "C15") (pin "1") (pinfunction "1_1") (pintype "input"))
      (node (ref "C2") (pin "1") (pinfunction "1_1") (pintype "input"))
      (node (ref "C24") (pin "2") (pinfunction "2_2") (pintype "input"))
      (node (ref "C26") (pin "2") (pinfunction "2_2") (pintype "input"))
      (node (ref "C27") (pin "1") (pinfunction "1_1") (pintype "input"))
      (node (ref "C28") (pin "1") (pinfunction "1_1") (pintype "input"))
      (node (ref "C3") (pin "1") (pinfunction "1_1") (pintype "input"))
      (node (ref "C33") (pin "1") (pinfunction "1_1") (pintype "input"))
      (node (ref "C34") (pin "1") (pinfunction "1_1") (pintype "input"))
      (node (ref "C4") (pin "2") (pinfunction "2_2") (pintype "input"))
      (node (ref "C5") (pin "2") (pinfunction "2_2") (pintype "input"))
      (node (ref "C8") (pin "1") (pinfunction "1_1") (pintype "input"))
      (node (ref "D2") (pin "2") (pinfunction "A_2") (pintype "input"))
      (node (ref "H1") (pin "13") (pinfunction "13_13") (pintype "input"))
      (node (ref "H1") (pin "14") (pinfunction "14_14") (pintype "input"))
      (node (ref "H1") (pin "15") (pinfunction "15_15") (pintype "input"))
      (node (ref "H1") (pin "16") (pinfunction "16_16") (pintype "input"))
      (node (ref "H1") (pin "17") (pinfunction "17_17") (pintype "input"))
      (node (ref "H1") (pin "3") (pinfunction "3_3") (pintype "input"))
      (node (ref "H3") (pin "13") (pinfunction "13_13") (pintype "input"))
      (node (ref "LED1") (pin "1") (pinfunction "-_1") (pintype "input"))
      (node (ref "R10") (pin "1") (pinfunction "1_1") (pintype "input"))
      (node (ref "R2") (pin "2") (pinfunction "2_2") (pintype "input"))
      (node (ref "R5") (pin "1") (pinfunction "1_1") (pintype "input"))
      (node (ref "R6") (pin "1") (pinfunction "1_1") (pintype "input"))
      (node (ref "U10") (pin "1") (pinfunction "GND/ADJ_1") (pintype "input"))
      (node (ref "U11") (pin "8") (pinfunction "GND_8") (pintype "input"))
      (node (ref "U2") (pin "13") (pinfunction "G_13") (pintype "input"))
      (node (ref "U3") (pin "7") (pinfunction "GND_7") (pintype "input"))
      (node (ref "U3") (pin "9") (pinfunction "EP_9") (pintype "input"))
      (node (ref "U5") (pin "8") (pinfunction "GND_8") (pintype "input"))
      (node (ref "U6") (pin "4") (pinfunction "GND_4") (pintype "input"))
      (node (ref "U6") (pin "7") (pinfunction "REF1_7") (pintype "input"))
      (node (ref "U7") (pin "4") (pinfunction "GND_4") (pintype "input"))
      (node (ref "U7") (pin "7") (pinfunction "REF1_7") (pintype "input"))
      (node (ref "U8") (pin "4") (pinfunction "GND_4") (pintype "input"))
      (node (ref "U8") (pin "7") (pinfunction "REF1_7") (pintype "input"))
      (node (ref "U9") (pin "4") (pinfunction "GND_4") (pintype "input"))
      (node (ref "U9") (pin "7") (pinfunction "REF1_7") (pintype "input"))
    )
    (net (code "40") (name "M0_IN1") (class "Default")
      (node (ref "H3") (pin "6") (pinfunction "6_6") (pintype "input"))
      (node (ref "U11") (pin "1") (pinfunction "HIN1_1") (pintype "input"))
      (node (ref "U11") (pin "4") (pinfunction "LIN1#_4") (pintype "input"))
      (node (ref "U2") (pin "6") (pinfunction "32_6") (pintype "input"))
    )
    (net (code "41") (name "M0_IN2") (class "Default")
      (node (ref "H3") (pin "7") (pinfunction "7_7") (pintype "input"))
      (node (ref "U11") (pin "2") (pinfunction "HIN2_2") (pintype "input"))
      (node (ref "U11") (pin "5") (pinfunction "LIN2#_5") (pintype "input"))
      (node (ref "U2") (pin "7") (pinfunction "33_7") (pintype "input"))
    )
    (net (code "42") (name "M0_IN3") (class "Default")
      (node (ref "H3") (pin "8") (pinfunction "8_8") (pintype "input"))
      (node (ref "U11") (pin "3") (pinfunction "HIN3_3") (pintype "input"))
      (node (ref "U11") (pin "6") (pinfunction "LIN3#_6") (pintype "input"))
      (node (ref "U2") (pin "8") (pinfunction "25_8") (pintype "input"))
    )
    (net (code "43") (name "M1_IN1") (class "Default")
      (node (ref "H3") (pin "9") (pinfunction "9_9") (pintype "input"))
      (node (ref "U2") (pin "9") (pinfunction "26_9") (pintype "input"))
      (node (ref "U5") (pin "1") (pinfunction "HIN1_1") (pintype "input"))
      (node (ref "U5") (pin "4") (pinfunction "LIN1#_4") (pintype "input"))
    )
    (net (code "44") (name "M1_IN2") (class "Default")
      (node (ref "H3") (pin "10") (pinfunction "10_10") (pintype "input"))
      (node (ref "U2") (pin "10") (pinfunction "27_10") (pintype "input"))
      (node (ref "U5") (pin "2") (pinfunction "HIN2_2") (pintype "input"))
      (node (ref "U5") (pin "5") (pinfunction "LIN2#_5") (pintype "input"))
    )
    (net (code "45") (name "M1_IN3") (class "Default")
      (node (ref "H3") (pin "11") (pinfunction "11_11") (pintype "input"))
      (node (ref "U2") (pin "11") (pinfunction "14_11") (pintype "input"))
      (node (ref "U5") (pin "3") (pinfunction "HIN3_3") (pintype "input"))
      (node (ref "U5") (pin "6") (pinfunction "LIN3#_6") (pintype "input"))
    )
    (net (code "46") (name "Net-(C14-Pad1)") (class "Default")
      (node (ref "C14") (pin "1") (pinfunction "1_1") (pintype "input"))
      (node (ref "R6") (pin "2") (pinfunction "2_2") (pintype "input"))
    )
    (net (code "47") (name "Net-(D2-K)") (class "Default")
      (node (ref "C17") (pin "1") (pinfunction "1_1") (pintype "input"))
      (node (ref "D2") (pin "1") (pinfunction "K_1") (pintype "input"))
      (node (ref "L1") (pin "1") (pinfunction "1_1") (pintype "input"))
      (node (ref "U3") (pin "8") (pinfunction "PH_8") (pintype "input"))
    )
    (net (code "48") (name "Net-(D4-C)") (class "Default")
      (node (ref "C9") (pin "1") (pinfunction "1_1") (pintype "input"))
      (node (ref "D4") (pin "1") (pinfunction "C_1") (pintype "input"))
      (node (ref "U5") (pin "20") (pinfunction "VB1_20") (pintype "input"))
    )
    (net (code "49") (name "Net-(D6-C)") (class "Default")
      (node (ref "C13") (pin "1") (pinfunction "1_1") (pintype "input"))
      (node (ref "D6") (pin "1") (pinfunction "C_1") (pintype "input"))
      (node (ref "U5") (pin "17") (pinfunction "VB2_17") (pintype "input"))
    )
    (net (code "50") (name "Net-(D7-C)") (class "Default")
      (node (ref "C16") (pin "1") (pinfunction "1_1") (pintype "input"))
      (node (ref "D7") (pin "1") (pinfunction "C_1") (pintype "input"))
      (node (ref "U5") (pin "14") (pinfunction "VB3_14") (pintype "input"))
    )
    (net (code "51") (name "Net-(D8-C)") (class "Default")
      (node (ref "C29") (pin "1") (pinfunction "1_1") (pintype "input"))
      (node (ref "D8") (pin "1") (pinfunction "C_1") (pintype "input"))
      (node (ref "U11") (pin "14") (pinfunction "VB3_14") (pintype "input"))
    )
    (net (code "52") (name "Net-(D9-C)") (class "Default")
      (node (ref "C23") (pin "1") (pinfunction "1_1") (pintype "input"))
      (node (ref "D9") (pin "1") (pinfunction "C_1") (pintype "input"))
      (node (ref "U11") (pin "17") (pinfunction "VB2_17") (pintype "input"))
    )
    (net (code "53") (name "Net-(D10-C)") (class "Default")
      (node (ref "C21") (pin "1") (pinfunction "1_1") (pintype "input"))
      (node (ref "D10") (pin "1") (pinfunction "C_1") (pintype "input"))
      (node (ref "U11") (pin "20") (pinfunction "VB1_20") (pintype "input"))
    )
    (net (code "54") (name "Net-(D11-C)") (class "Default")
      (node (ref "D11") (pin "1") (pinfunction "C_1") (pintype "input"))
      (node (ref "H2") (pin "1") (pinfunction "1_1") (pintype "input"))
    )
    (net (code "55") (name "Net-(LED1-+)") (class "Default")
      (node (ref "LED1") (pin "2") (pinfunction "+_2") (pintype "input"))
      (node (ref "R3") (pin "2") (pinfunction "2_2") (pintype "input"))
    )
    (net (code "56") (name "Net-(Q1-G)") (class "Default")
      (node (ref "Q1") (pin "4") (pinfunction "G_4") (pintype "input"))
      (node (ref "R27") (pin "2") (pinfunction "2_2") (pintype "input"))
      (node (ref "R28") (pin "1") (pinfunction "1_1") (pintype "input"))
    )
    (net (code "57") (name "Net-(Q2-G)") (class "Default")
      (node (ref "Q2") (pin "4") (pinfunction "G_4") (pintype "input"))
      (node (ref "R26") (pin "2") (pinfunction "2_2") (pintype "input"))
      (node (ref "R29") (pin "1") (pinfunction "1_1") (pintype "input"))
    )
    (net (code "58") (name "Net-(Q3-G)") (class "Default")
      (node (ref "Q3") (pin "4") (pinfunction "G_4") (pintype "input"))
      (node (ref "R24") (pin "2") (pinfunction "2_2") (pintype "input"))
      (node (ref "R31") (pin "1") (pinfunction "1_1") (pintype "input"))
    )
    (net (code "59") (name "Net-(Q4-G)") (class "Default")
      (node (ref "Q4") (pin "4") (pinfunction "G_4") (pintype "input"))
      (node (ref "R25") (pin "2") (pinfunction "2_2") (pintype "input"))
      (node (ref "R30") (pin "1") (pinfunction "1_1") (pintype "input"))
    )
    (net (code "60") (name "Net-(Q5-G)") (class "Default")
      (node (ref "Q5") (pin "4") (pinfunction "G_4") (pintype "input"))
      (node (ref "R22") (pin "2") (pinfunction "2_2") (pintype "input"))
      (node (ref "R32") (pin "1") (pinfunction "1_1") (pintype "input"))
    )
    (net (code "61") (name "Net-(Q6-G)") (class "Default")
      (node (ref "Q6") (pin "4") (pinfunction "G_4") (pintype "input"))
      (node (ref "R23") (pin "2") (pinfunction "2_2") (pintype "input"))
      (node (ref "R33") (pin "1") (pinfunction "1_1") (pintype "input"))
    )
    (net (code "62") (name "Net-(Q7-G)") (class "Default")
      (node (ref "Q7") (pin "4") (pinfunction "G_4") (pintype "input"))
      (node (ref "R14") (pin "2") (pinfunction "2_2") (pintype "input"))
      (node (ref "R34") (pin "1") (pinfunction "1_1") (pintype "input"))
    )
    (net (code "63") (name "Net-(Q8-G)") (class "Default")
      (node (ref "Q8") (pin "4") (pinfunction "G_4") (pintype "input"))
      (node (ref "R13") (pin "2") (pinfunction "2_2") (pintype "input"))
      (node (ref "R35") (pin "1") (pinfunction "1_1") (pintype "input"))
    )
    (net (code "64") (name "Net-(Q9-G)") (class "Default")
      (node (ref "Q9") (pin "4") (pinfunction "G_4") (pintype "input"))
      (node (ref "R11") (pin "2") (pinfunction "2_2") (pintype "input"))
      (node (ref "R36") (pin "1") (pinfunction "1_1") (pintype "input"))
    )
    (net (code "65") (name "Net-(Q10-G)") (class "Default")
      (node (ref "Q10") (pin "4") (pinfunction "G_4") (pintype "input"))
      (node (ref "R12") (pin "2") (pinfunction "2_2") (pintype "input"))
      (node (ref "R37") (pin "1") (pinfunction "1_1") (pintype "input"))
    )
    (net (code "66") (name "Net-(Q11-G)") (class "Default")
      (node (ref "Q11") (pin "4") (pinfunction "G_4") (pintype "input"))
      (node (ref "R21") (pin "2") (pinfunction "2_2") (pintype "input"))
      (node (ref "R39") (pin "1") (pinfunction "1_1") (pintype "input"))
    )
    (net (code "67") (name "Net-(Q12-G)") (class "Default")
      (node (ref "Q12") (pin "4") (pinfunction "G_4") (pintype "input"))
      (node (ref "R20") (pin "2") (pinfunction "2_2") (pintype "input"))
      (node (ref "R38") (pin "1") (pinfunction "1_1") (pintype "input"))
    )
    (net (code "68") (name "Net-(U3-BOOT)") (class "Default")
      (node (ref "C17") (pin "2") (pinfunction "2_2") (pintype "input"))
      (node (ref "U3") (pin "1") (pinfunction "BOOT_1") (pintype "input"))
    )
    (net (code "69") (name "Net-(U3-COMP)") (class "Default")
      (node (ref "C14") (pin "2") (pinfunction "2_2") (pintype "input"))
      (node (ref "C15") (pin "2") (pinfunction "2_2") (pintype "input"))
      (node (ref "U3") (pin "6") (pinfunction "COMP_6") (pintype "input"))
    )
    (net (code "70") (name "Net-(U3-EN)") (class "Default")
      (node (ref "R4") (pin "1") (pinfunction "1_1") (pintype "input"))
      (node (ref "R5") (pin "2") (pinfunction "2_2") (pintype "input"))
      (node (ref "U3") (pin "3") (pinfunction "EN_3") (pintype "input"))
    )
    (net (code "71") (name "Net-(U3-SS)") (class "Default")
      (node (ref "C12") (pin "2") (pinfunction "2_2") (pintype "input"))
      (node (ref "U3") (pin "4") (pinfunction "SS_4") (pintype "input"))
    )
    (net (code "72") (name "Net-(U3-VSENSE)") (class "Default")
      (node (ref "R10") (pin "2") (pinfunction "2_2") (pintype "input"))
      (node (ref "R9") (pin "1") (pinfunction "1_1") (pintype "input"))
      (node (ref "U3") (pin "5") (pinfunction "VSENSE_5") (pintype "input"))
    )
    (net (code "73") (name "PGND") (class "Default")
      (node (ref "C11") (pin "1") (pinfunction "1_1") (pintype "input"))
      (node (ref "C18") (pin "1") (pinfunction "1_1") (pintype "input"))
      (node (ref "C19") (pin "1") (pinfunction "1_1") (pintype "input"))
      (node (ref "C25") (pin "1") (pinfunction "1_1") (pintype "input"))
      (node (ref "C30") (pin "1") (pinfunction "1_1") (pintype "input"))
      (node (ref "C31") (pin "1") (pinfunction "1_1") (pintype "input"))
      (node (ref "C32") (pin "1") (pinfunction "1_1") (pintype "input"))
      (node (ref "C35") (pin "2") (pinfunction "2_2") (pintype "input"))
      (node (ref "C36") (pin "2") (pinfunction "2_2") (pintype "input"))
      (node (ref "C7") (pin "1") (pinfunction "1_1") (pintype "input"))
      (node (ref "P3") (pin "1") (pinfunction "1_1") (pintype "input"))
      (node (ref "Q10") (pin "1") (pinfunction "S_1") (pintype "input"))
      (node (ref "Q10") (pin "2") (pinfunction "S_2") (pintype "input"))
      (node (ref "Q10") (pin "3") (pinfunction "S_3") (pintype "input"))
      (node (ref "Q12") (pin "1") (pinfunction "S_1") (pintype "input"))
      (node (ref "Q12") (pin "2") (pinfunction "S_2") (pintype "input"))
      (node (ref "Q12") (pin "3") (pinfunction "S_3") (pintype "input"))
      (node (ref "Q2") (pin "1") (pinfunction "S_1") (pintype "input"))
      (node (ref "Q2") (pin "2") (pinfunction "S_2") (pintype "input"))
      (node (ref "Q2") (pin "3") (pinfunction "S_3") (pintype "input"))
      (node (ref "Q4") (pin "1") (pinfunction "S_1") (pintype "input"))
      (node (ref "Q4") (pin "2") (pinfunction "S_2") (pintype "input"))
      (node (ref "Q4") (pin "3") (pinfunction "S_3") (pintype "input"))
      (node (ref "Q6") (pin "1") (pinfunction "S_1") (pintype "input"))
      (node (ref "Q6") (pin "2") (pinfunction "S_2") (pintype "input"))
      (node (ref "Q6") (pin "3") (pinfunction "S_3") (pintype "input"))
      (node (ref "Q8") (pin "1") (pinfunction "S_1") (pintype "input"))
      (node (ref "Q8") (pin "2") (pinfunction "S_2") (pintype "input"))
      (node (ref "Q8") (pin "3") (pinfunction "S_3") (pintype "input"))
      (node (ref "R2") (pin "1") (pinfunction "1_1") (pintype "input"))
      (node (ref "R29") (pin "2") (pinfunction "2_2") (pintype "input"))
      (node (ref "R30") (pin "2") (pinfunction "2_2") (pintype "input"))
      (node (ref "R33") (pin "2") (pinfunction "2_2") (pintype "input"))
      (node (ref "R35") (pin "2") (pinfunction "2_2") (pintype "input"))
      (node (ref "R37") (pin "2") (pinfunction "2_2") (pintype "input"))
      (node (ref "R38") (pin "2") (pinfunction "2_2") (pintype "input"))
    )
    (net (code "74") (name "VIN") (class "Default")
      (node (ref "C10") (pin "1") (pinfunction "1_1") (pintype "input"))
      (node (ref "C11") (pin "2") (pinfunction "2_2") (pintype "input"))
      (node (ref "C18") (pin "2") (pinfunction "2_2") (pintype "input"))
      (node (ref "C19") (pin "2") (pinfunction "2_2") (pintype "input"))
      (node (ref "C25") (pin "2") (pinfunction "2_2") (pintype "input"))
      (node (ref "C3") (pin "2") (pinfunction "2_2") (pintype "input"))
      (node (ref "C30") (pin "2") (pinfunction "2_2") (pintype "input"))
      (node (ref "C31") (pin "2") (pinfunction "2_2") (pintype "input"))
      (node (ref "C32") (pin "2") (pinfunction "2_2") (pintype "input"))
      (node (ref "C35") (pin "1") (pinfunction "1_1") (pintype "input"))
      (node (ref "C36") (pin "1") (pinfunction "1_1") (pintype "input"))
      (node (ref "C7") (pin "2") (pinfunction "2_2") (pintype "input"))
      (node (ref "C8") (pin "2") (pinfunction "2_2") (pintype "input"))
      (node (ref "P3") (pin "2") (pinfunction "2_2") (pintype "input"))
      (node (ref "Q1") (pin "5") (pinfunction "D_5") (pintype "input"))
      (node (ref "Q1") (pin "6") (pinfunction "D_6") (pintype "input"))
      (node (ref "Q1") (pin "7") (pinfunction "D_7") (pintype "input"))
      (node (ref "Q1") (pin "8") (pinfunction "D_8") (pintype "input"))
      (node (ref "Q1") (pin "9") (pinfunction "D_9") (pintype "input"))
      (node (ref "Q11") (pin "5") (pinfunction "D_5") (pintype "input"))
      (node (ref "Q11") (pin "6") (pinfunction "D_6") (pintype "input"))
      (node (ref "Q11") (pin "7") (pinfunction "D_7") (pintype "input"))
      (node (ref "Q11") (pin "8") (pinfunction "D_8") (pintype "input"))
      (node (ref "Q11") (pin "9") (pinfunction "D_9") (pintype "input"))
      (node (ref "Q3") (pin "5") (pinfunction "D_5") (pintype "input"))
      (node (ref "Q3") (pin "6") (pinfunction "D_6") (pintype "input"))
      (node (ref "Q3") (pin "7") (pinfunction "D_7") (pintype "input"))
      (node (ref "Q3") (pin "8") (pinfunction "D_8") (pintype "input"))
      (node (ref "Q3") (pin "9") (pinfunction "D_9") (pintype "input"))
      (node (ref "Q5") (pin "5") (pinfunction "D_5") (pintype "input"))
      (node (ref "Q5") (pin "6") (pinfunction "D_6") (pintype "input"))
      (node (ref "Q5") (pin "7") (pinfunction "D_7") (pintype "input"))
      (node (ref "Q5") (pin "8") (pinfunction "D_8") (pintype "input"))
      (node (ref "Q5") (pin "9") (pinfunction "D_9") (pintype "input"))
      (node (ref "Q7") (pin "5") (pinfunction "D_5") (pintype "input"))
      (node (ref "Q7") (pin "6") (pinfunction "D_6") (pintype "input"))
      (node (ref "Q7") (pin "7") (pinfunction "D_7") (pintype "input"))
      (node (ref "Q7") (pin "8") (pinfunction "D_8") (pintype "input"))
      (node (ref "Q7") (pin "9") (pinfunction "D_9") (pintype "input"))
      (node (ref "Q9") (pin "5") (pinfunction "D_5") (pintype "input"))
      (node (ref "Q9") (pin "6") (pinfunction "D_6") (pintype "input"))
      (node (ref "Q9") (pin "7") (pinfunction "D_7") (pintype "input"))
      (node (ref "Q9") (pin "8") (pinfunction "D_8") (pintype "input"))
      (node (ref "Q9") (pin "9") (pinfunction "D_9") (pintype "input"))
      (node (ref "R4") (pin "2") (pinfunction "2_2") (pintype "input"))
      (node (ref "U3") (pin "2") (pinfunction "VIN_2") (pintype "input"))
    )
    (net (code "75") (name "unconnected-(H2-Pad9)") (class "Default")
      (node (ref "H2") (pin "9") (pinfunction "9_9") (pintype "input+no_connect"))
    )
    (net (code "76") (name "unconnected-(H2-Pad10)") (class "Default")
      (node (ref "H2") (pin "10") (pinfunction "10_10") (pintype "input+no_connect"))
    )
    (net (code "77") (name "unconnected-(H2-Pad11)") (class "Default")
      (node (ref "H2") (pin "11") (pinfunction "11_11") (pintype "input+no_connect"))
    )
    (net (code "78") (name "unconnected-(H3-Pad3)") (class "Default")
      (node (ref "H3") (pin "3") (pinfunction "3_3") (pintype "input+no_connect"))
    )
    (net (code "79") (name "unconnected-(U2-0-Pad23)") (class "Default")
      (node (ref "U2") (pin "23") (pinfunction "0_23") (pintype "input"))
    )
    (net (code "80") (name "unconnected-(U2-2-Pad24)") (class "Default")
      (node (ref "U2") (pin "24") (pinfunction "2_24") (pintype "input"))
    )
    (net (code "81") (name "unconnected-(U2-3V-Pad14)") (class "Default")
      (node (ref "U2") (pin "14") (pinfunction "3V_14") (pintype "input"))
    )
    (net (code "82") (name "unconnected-(U2-4-Pad22)") (class "Default")
      (node (ref "U2") (pin "22") (pinfunction "4_22") (pintype "input"))
    )
    (net (code "83") (name "unconnected-(U2-15-Pad25)") (class "Default")
      (node (ref "U2") (pin "25") (pinfunction "15_25") (pintype "input"))
    )
    (net (code "84") (name "unconnected-(U2-EN-Pad3)") (class "Default")
      (node (ref "U2") (pin "3") (pinfunction "EN_3") (pintype "input"))
    )
    (net (code "85") (name "unconnected-(U6-NC-Pad1)") (class "Default")
      (node (ref "U6") (pin "1") (pinfunction "NC_1") (pintype "input"))
    )
    (net (code "86") (name "unconnected-(U7-NC-Pad1)") (class "Default")
      (node (ref "U7") (pin "1") (pinfunction "NC_1") (pintype "input"))
    )
    (net (code "87") (name "unconnected-(U8-NC-Pad1)") (class "Default")
      (node (ref "U8") (pin "1") (pinfunction "NC_1") (pintype "input"))
    )
    (net (code "88") (name "unconnected-(U9-NC-Pad1)") (class "Default")
      (node (ref "U9") (pin "1") (pinfunction "NC_1") (pintype "input"))
    )
  )
)
